# RowDotMatrix.net
KiCad netlist of a schematic drawn in Altium Designer
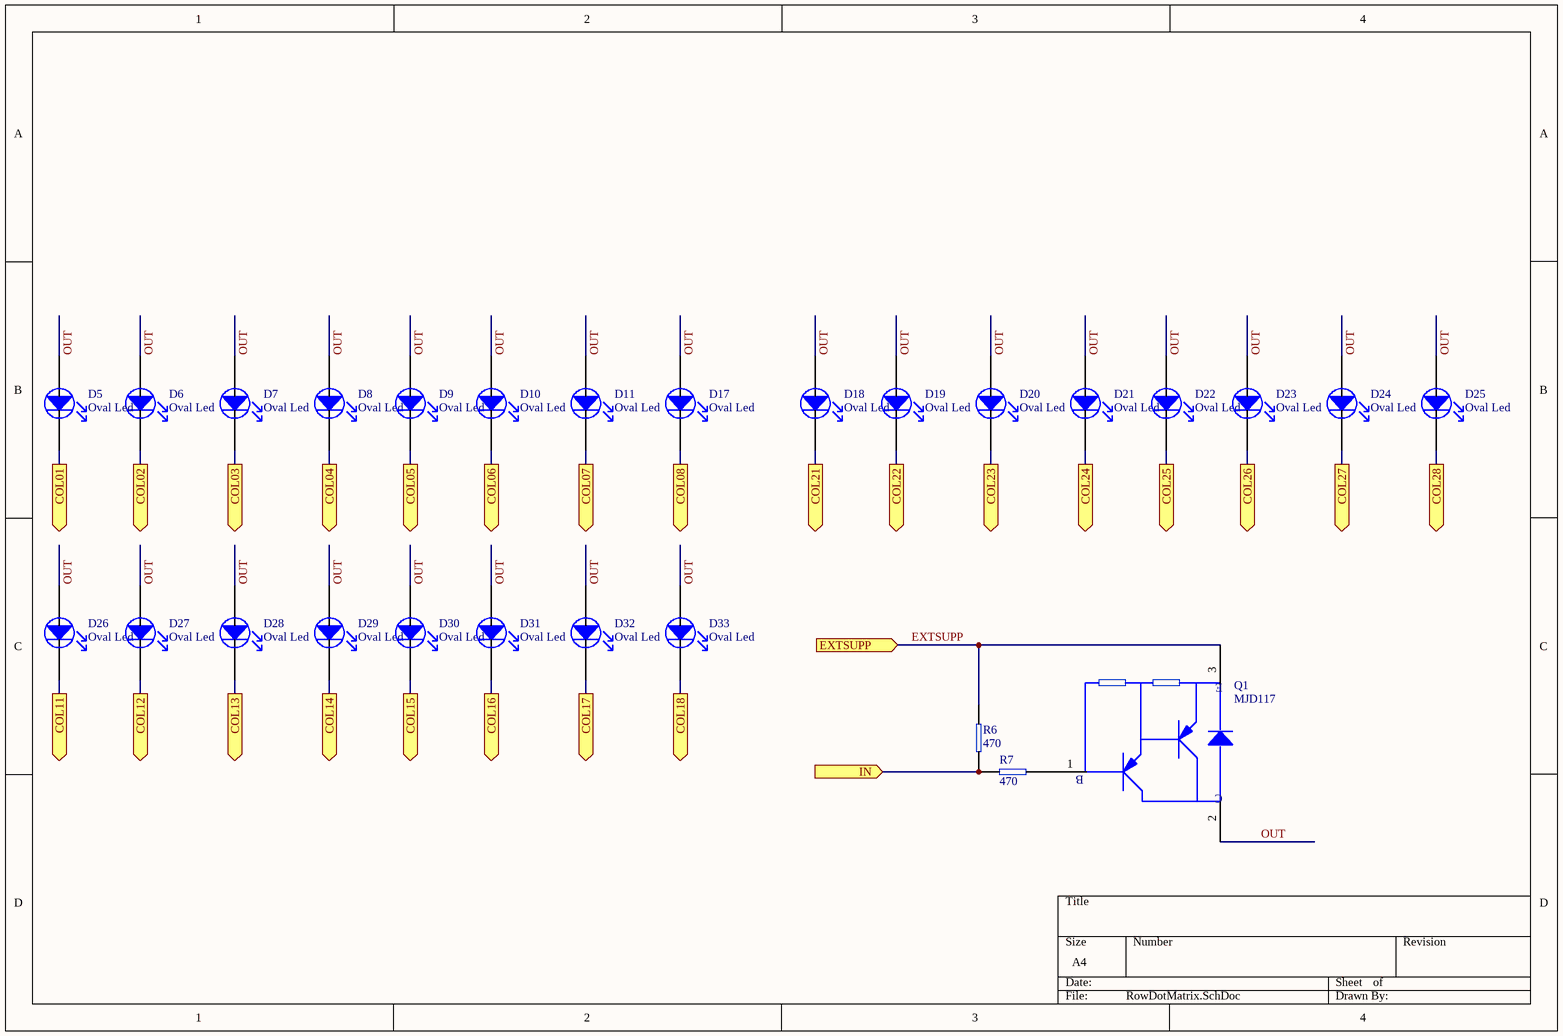
[diagram p0: RowDotMatrix.SchDoc]

(export (version "E")
  (design (tool "Eeschema 10.0.6"))
  (components
    (comp (ref "D5")
      (value "Oval Led")
      (footprint "LED")
      (description "LED estándar - Montaje interfacial Red Oval LED")
      (fields (field (name "MPN") "C566C-RFN-CV0W0BB2"))
      (libsource (lib "techdev") (part "Oval Led"))
    )
    (comp (ref "D6")
      (value "Oval Led")
      (footprint "LED")
      (description "LED estándar - Montaje interfacial Red Oval LED")
      (fields (field (name "MPN") "C566C-RFN-CV0W0BB2"))
      (libsource (lib "techdev") (part "Oval Led"))
    )
    (comp (ref "D7")
      (value "Oval Led")
      (footprint "LED")
      (description "LED estándar - Montaje interfacial Red Oval LED")
      (fields (field (name "MPN") "C566C-RFN-CV0W0BB2"))
      (libsource (lib "techdev") (part "Oval Led"))
    )
    (comp (ref "D8")
      (value "Oval Led")
      (footprint "LED")
      (description "LED estándar - Montaje interfacial Red Oval LED")
      (fields (field (name "MPN") "C566C-RFN-CV0W0BB2"))
      (libsource (lib "techdev") (part "Oval Led"))
    )
    (comp (ref "D9")
      (value "Oval Led")
      (footprint "LED")
      (description "LED estándar - Montaje interfacial Red Oval LED")
      (fields (field (name "MPN") "C566C-RFN-CV0W0BB2"))
      (libsource (lib "techdev") (part "Oval Led"))
    )
    (comp (ref "D10")
      (value "Oval Led")
      (footprint "LED")
      (description "LED estándar - Montaje interfacial Red Oval LED")
      (fields (field (name "MPN") "C566C-RFN-CV0W0BB2"))
      (libsource (lib "techdev") (part "Oval Led"))
    )
    (comp (ref "D11")
      (value "Oval Led")
      (footprint "LED")
      (description "LED estándar - Montaje interfacial Red Oval LED")
      (fields (field (name "MPN") "C566C-RFN-CV0W0BB2"))
      (libsource (lib "techdev") (part "Oval Led"))
    )
    (comp (ref "D17")
      (value "Oval Led")
      (footprint "LED")
      (description "LED estándar - Montaje interfacial Red Oval LED")
      (fields (field (name "MPN") "C566C-RFN-CV0W0BB2"))
      (libsource (lib "techdev") (part "Oval Led"))
    )
    (comp (ref "D18")
      (value "Oval Led")
      (footprint "LED")
      (description "LED estándar - Montaje interfacial Red Oval LED")
      (fields (field (name "MPN") "C566C-RFN-CV0W0BB2"))
      (libsource (lib "techdev") (part "Oval Led"))
    )
    (comp (ref "D19")
      (value "Oval Led")
      (footprint "LED")
      (description "LED estándar - Montaje interfacial Red Oval LED")
      (fields (field (name "MPN") "C566C-RFN-CV0W0BB2"))
      (libsource (lib "techdev") (part "Oval Led"))
    )
    (comp (ref "D20")
      (value "Oval Led")
      (footprint "LED")
      (description "LED estándar - Montaje interfacial Red Oval LED")
      (fields (field (name "MPN") "C566C-RFN-CV0W0BB2"))
      (libsource (lib "techdev") (part "Oval Led"))
    )
    (comp (ref "D21")
      (value "Oval Led")
      (footprint "LED")
      (description "LED estándar - Montaje interfacial Red Oval LED")
      (fields (field (name "MPN") "C566C-RFN-CV0W0BB2"))
      (libsource (lib "techdev") (part "Oval Led"))
    )
    (comp (ref "D22")
      (value "Oval Led")
      (footprint "LED")
      (description "LED estándar - Montaje interfacial Red Oval LED")
      (fields (field (name "MPN") "C566C-RFN-CV0W0BB2"))
      (libsource (lib "techdev") (part "Oval Led"))
    )
    (comp (ref "D23")
      (value "Oval Led")
      (footprint "LED")
      (description "LED estándar - Montaje interfacial Red Oval LED")
      (fields (field (name "MPN") "C566C-RFN-CV0W0BB2"))
      (libsource (lib "techdev") (part "Oval Led"))
    )
    (comp (ref "D24")
      (value "Oval Led")
      (footprint "LED")
      (description "LED estándar - Montaje interfacial Red Oval LED")
      (fields (field (name "MPN") "C566C-RFN-CV0W0BB2"))
      (libsource (lib "techdev") (part "Oval Led"))
    )
    (comp (ref "D25")
      (value "Oval Led")
      (footprint "LED")
      (description "LED estándar - Montaje interfacial Red Oval LED")
      (fields (field (name "MPN") "C566C-RFN-CV0W0BB2"))
      (libsource (lib "techdev") (part "Oval Led"))
    )
    (comp (ref "D26")
      (value "Oval Led")
      (footprint "LED")
      (description "LED estándar - Montaje interfacial Red Oval LED")
      (fields (field (name "MPN") "C566C-RFN-CV0W0BB2"))
      (libsource (lib "techdev") (part "Oval Led"))
    )
    (comp (ref "D27")
      (value "Oval Led")
      (footprint "LED")
      (description "LED estándar - Montaje interfacial Red Oval LED")
      (fields (field (name "MPN") "C566C-RFN-CV0W0BB2"))
      (libsource (lib "techdev") (part "Oval Led"))
    )
    (comp (ref "D28")
      (value "Oval Led")
      (footprint "LED")
      (description "LED estándar - Montaje interfacial Red Oval LED")
      (fields (field (name "MPN") "C566C-RFN-CV0W0BB2"))
      (libsource (lib "techdev") (part "Oval Led"))
    )
    (comp (ref "D29")
      (value "Oval Led")
      (footprint "LED")
      (description "LED estándar - Montaje interfacial Red Oval LED")
      (fields (field (name "MPN") "C566C-RFN-CV0W0BB2"))
      (libsource (lib "techdev") (part "Oval Led"))
    )
    (comp (ref "D30")
      (value "Oval Led")
      (footprint "LED")
      (description "LED estándar - Montaje interfacial Red Oval LED")
      (fields (field (name "MPN") "C566C-RFN-CV0W0BB2"))
      (libsource (lib "techdev") (part "Oval Led"))
    )
    (comp (ref "D31")
      (value "Oval Led")
      (footprint "LED")
      (description "LED estándar - Montaje interfacial Red Oval LED")
      (fields (field (name "MPN") "C566C-RFN-CV0W0BB2"))
      (libsource (lib "techdev") (part "Oval Led"))
    )
    (comp (ref "D32")
      (value "Oval Led")
      (footprint "LED")
      (description "LED estándar - Montaje interfacial Red Oval LED")
      (fields (field (name "MPN") "C566C-RFN-CV0W0BB2"))
      (libsource (lib "techdev") (part "Oval Led"))
    )
    (comp (ref "D33")
      (value "Oval Led")
      (footprint "LED")
      (description "LED estándar - Montaje interfacial Red Oval LED")
      (fields (field (name "MPN") "C566C-RFN-CV0W0BB2"))
      (libsource (lib "techdev") (part "Oval Led"))
    )
    (comp (ref "Q1")
      (value "MJD117")
      (footprint "MJD117")
      (description "Transistores Darlington PNP Silicon Darl")
      (fields (field (name "MPN") "MJD117TF"))
      (libsource (lib "Miscellaneous Devices") (part "MJD117"))
    )
    (comp (ref "R6")
      (value "470")
      (footprint "RES2512")
      (description "Resistores de película gruesa - SMD 1watt 470ohms 5%")
      (fields (field (name "MPN") "CRCW2512470RJNEG") (field (name "Comment") "RES470"))
      (libsource (lib "Miscellaneous Devices") (part "RES470"))
    )
    (comp (ref "R7")
      (value "470")
      (footprint "RES2512")
      (description "Resistores de película gruesa - SMD 1watt 470ohms 5%")
      (fields (field (name "MPN") "CRCW2512470RJNEG") (field (name "Comment") "RES470"))
      (libsource (lib "") (part "RES470_1"))
    )
  )
  (nets
    (net (code "1") (name "/COL01") (class "Default")
      (node (ref "D5") (pin "K") (pinfunction "Cathode_K") (pintype "passive"))
    )
    (net (code "2") (name "/COL02") (class "Default")
      (node (ref "D6") (pin "K") (pinfunction "Cathode_K") (pintype "passive"))
    )
    (net (code "3") (name "/COL03") (class "Default")
      (node (ref "D7") (pin "K") (pinfunction "Cathode_K") (pintype "passive"))
    )
    (net (code "4") (name "/COL04") (class "Default")
      (node (ref "D8") (pin "K") (pinfunction "Cathode_K") (pintype "passive"))
    )
    (net (code "5") (name "/COL05") (class "Default")
      (node (ref "D9") (pin "K") (pinfunction "Cathode_K") (pintype "passive"))
    )
    (net (code "6") (name "/COL06") (class "Default")
      (node (ref "D10") (pin "K") (pinfunction "Cathode_K") (pintype "passive"))
    )
    (net (code "7") (name "/COL07") (class "Default")
      (node (ref "D11") (pin "K") (pinfunction "Cathode_K") (pintype "passive"))
    )
    (net (code "8") (name "/COL08") (class "Default")
      (node (ref "D17") (pin "K") (pinfunction "Cathode_K") (pintype "passive"))
    )
    (net (code "9") (name "/COL11") (class "Default")
      (node (ref "D26") (pin "K") (pinfunction "Cathode_K") (pintype "passive"))
    )
    (net (code "10") (name "/COL12") (class "Default")
      (node (ref "D27") (pin "K") (pinfunction "Cathode_K") (pintype "passive"))
    )
    (net (code "11") (name "/COL13") (class "Default")
      (node (ref "D28") (pin "K") (pinfunction "Cathode_K") (pintype "passive"))
    )
    (net (code "12") (name "/COL14") (class "Default")
      (node (ref "D29") (pin "K") (pinfunction "Cathode_K") (pintype "passive"))
    )
    (net (code "13") (name "/COL15") (class "Default")
      (node (ref "D30") (pin "K") (pinfunction "Cathode_K") (pintype "passive"))
    )
    (net (code "14") (name "/COL16") (class "Default")
      (node (ref "D31") (pin "K") (pinfunction "Cathode_K") (pintype "passive"))
    )
    (net (code "15") (name "/COL17") (class "Default")
      (node (ref "D32") (pin "K") (pinfunction "Cathode_K") (pintype "passive"))
    )
    (net (code "16") (name "/COL18") (class "Default")
      (node (ref "D33") (pin "K") (pinfunction "Cathode_K") (pintype "passive"))
    )
    (net (code "17") (name "/COL21") (class "Default")
      (node (ref "D18") (pin "K") (pinfunction "Cathode_K") (pintype "passive"))
    )
    (net (code "18") (name "/COL22") (class "Default")
      (node (ref "D19") (pin "K") (pinfunction "Cathode_K") (pintype "passive"))
    )
    (net (code "19") (name "/COL23") (class "Default")
      (node (ref "D20") (pin "K") (pinfunction "Cathode_K") (pintype "passive"))
    )
    (net (code "20") (name "/COL24") (class "Default")
      (node (ref "D21") (pin "K") (pinfunction "Cathode_K") (pintype "passive"))
    )
    (net (code "21") (name "/COL25") (class "Default")
      (node (ref "D22") (pin "K") (pinfunction "Cathode_K") (pintype "passive"))
    )
    (net (code "22") (name "/COL26") (class "Default")
      (node (ref "D23") (pin "K") (pinfunction "Cathode_K") (pintype "passive"))
    )
    (net (code "23") (name "/COL27") (class "Default")
      (node (ref "D24") (pin "K") (pinfunction "Cathode_K") (pintype "passive"))
    )
    (net (code "24") (name "/COL28") (class "Default")
      (node (ref "D25") (pin "K") (pinfunction "Cathode_K") (pintype "passive"))
    )
    (net (code "25") (name "/EXTSUPP") (class "Default")
      (node (ref "Q1") (pin "3") (pinfunction "E_3") (pintype "passive"))
      (node (ref "R6") (pin "1") (pinfunction "pos_1") (pintype "passive"))
    )
    (net (code "26") (name "/IN") (class "Default")
      (node (ref "R6") (pin "2") (pinfunction "neg_2") (pintype "passive"))
      (node (ref "R7") (pin "1") (pinfunction "pos_1") (pintype "passive"))
    )
    (net (code "27") (name "/OUT") (class "Default")
      (node (ref "D10") (pin "A") (pinfunction "Anode_A") (pintype "passive"))
      (node (ref "D11") (pin "A") (pinfunction "Anode_A") (pintype "passive"))
      (node (ref "D17") (pin "A") (pinfunction "Anode_A") (pintype "passive"))
      (node (ref "D18") (pin "A") (pinfunction "Anode_A") (pintype "passive"))
      (node (ref "D19") (pin "A") (pinfunction "Anode_A") (pintype "passive"))
      (node (ref "D20") (pin "A") (pinfunction "Anode_A") (pintype "passive"))
      (node (ref "D21") (pin "A") (pinfunction "Anode_A") (pintype "passive"))
      (node (ref "D22") (pin "A") (pinfunction "Anode_A") (pintype "passive"))
      (node (ref "D23") (pin "A") (pinfunction "Anode_A") (pintype "passive"))
      (node (ref "D24") (pin "A") (pinfunction "Anode_A") (pintype "passive"))
      (node (ref "D25") (pin "A") (pinfunction "Anode_A") (pintype "passive"))
      (node (ref "D26") (pin "A") (pinfunction "Anode_A") (pintype "passive"))
      (node (ref "D27") (pin "A") (pinfunction "Anode_A") (pintype "passive"))
      (node (ref "D28") (pin "A") (pinfunction "Anode_A") (pintype "passive"))
      (node (ref "D29") (pin "A") (pinfunction "Anode_A") (pintype "passive"))
      (node (ref "D30") (pin "A") (pinfunction "Anode_A") (pintype "passive"))
      (node (ref "D31") (pin "A") (pinfunction "Anode_A") (pintype "passive"))
      (node (ref "D32") (pin "A") (pinfunction "Anode_A") (pintype "passive"))
      (node (ref "D33") (pin "A") (pinfunction "Anode_A") (pintype "passive"))
      (node (ref "D5") (pin "A") (pinfunction "Anode_A") (pintype "passive"))
      (node (ref "D6") (pin "A") (pinfunction "Anode_A") (pintype "passive"))
      (node (ref "D7") (pin "A") (pinfunction "Anode_A") (pintype "passive"))
      (node (ref "D8") (pin "A") (pinfunction "Anode_A") (pintype "passive"))
      (node (ref "D9") (pin "A") (pinfunction "Anode_A") (pintype "passive"))
      (node (ref "Q1") (pin "2") (pinfunction "C_2") (pintype "passive"))
    )
    (net (code "28") (name "Net-(Q1-B)") (class "Default")
      (node (ref "Q1") (pin "1") (pinfunction "B_1") (pintype "passive"))
      (node (ref "R7") (pin "2") (pinfunction "neg_2") (pintype "passive"))
    )
  )
)
